# MCU.net
KiCad netlist of a schematic drawn in Altium Designer
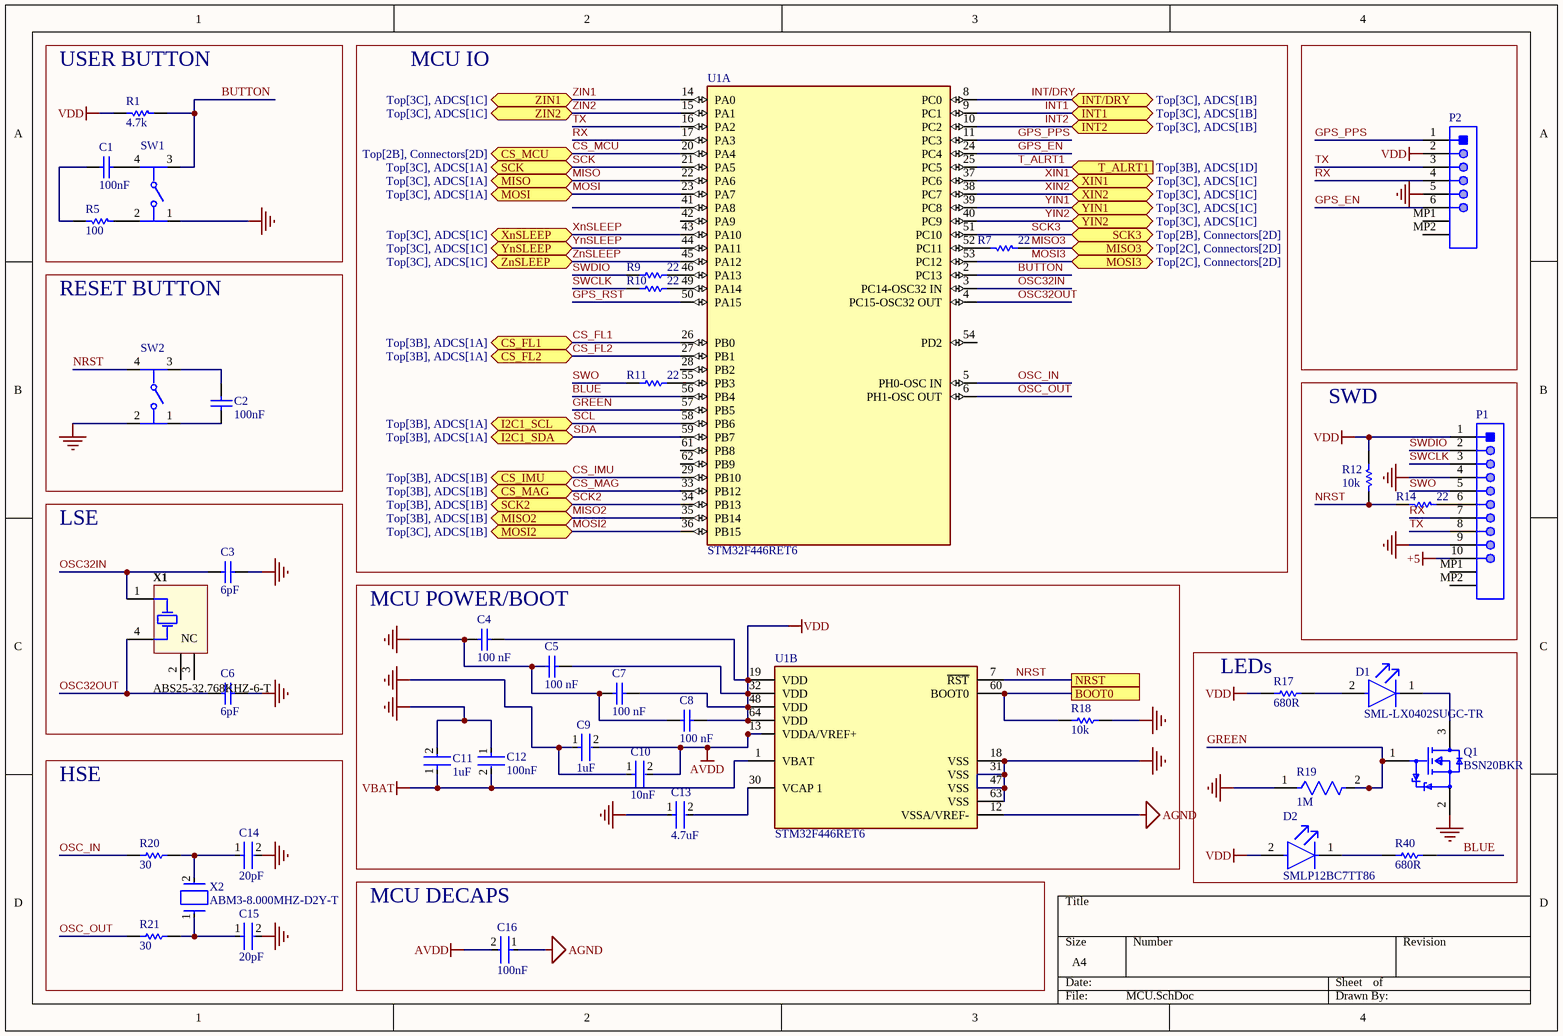
[diagram p0: MCU.SchDoc]

(export (version "E")
  (design (tool "Eeschema 10.0.6"))
  (components
    (comp (ref "C1")
      (value "100nF")
      (footprint "CAPC1050X55X23ML05T13")
      (description "Chip Capacitor, 100 nF, +/- 10%, 16 V, -55 to 125 degC, 0402 (1005 Metric), RoHS, Tape and Reel")
      (fields (field (name "MANUFACTURER") "Samsung Electro-Mechanics"))
      (libsource (lib "Altium Content Vault") (part "CAP-NP-2"))
    )
    (comp (ref "C2")
      (value "100nF")
      (footprint "CAPC1050X55X23ML05T13")
      (description "Chip Capacitor, 100 nF, +/- 10%, 16 V, -55 to 125 degC, 0402 (1005 Metric), RoHS, Tape and Reel")
      (fields (field (name "MANUFACTURER") "Samsung Electro-Mechanics"))
      (libsource (lib "Altium Content Vault") (part "CAP-NP-2"))
    )
    (comp (ref "C3")
      (value "6pF")
      (footprint "CAPC1005X55X25ML05T10")
      (fields (field (name "PART NUMBER") "GRM1555C1H6R0DA01D") (field (name "MANUFACTURER") "Murata"))
      (libsource (lib "Altium Content Vault") (part "CAP"))
    )
    (comp (ref "C4")
      (value "100 nF")
      (footprint "CAPC1050X55X23ML05T13")
      (description "Chip Capacitor, 100 nF, +/- 10%, 16 V, -55 to 125 degC, 0402 (1005 Metric), RoHS, Tape and Reel")
      (fields (field (name "MANUFACTURER") "Samsung Electro-Mechanics"))
      (libsource (lib "Altium Content Vault") (part "CAP-NP-2"))
    )
    (comp (ref "C5")
      (value "100 nF")
      (footprint "CAPC1050X55X23ML05T13")
      (description "Chip Capacitor, 100 nF, +/- 10%, 16 V, -55 to 125 degC, 0402 (1005 Metric), RoHS, Tape and Reel")
      (fields (field (name "MANUFACTURER") "Samsung Electro-Mechanics"))
      (libsource (lib "Altium Content Vault") (part "CAP-NP-2"))
    )
    (comp (ref "C6")
      (value "6pF")
      (footprint "CAPC1005X55X25ML05T10")
      (fields (field (name "PART NUMBER") "GRM1555C1H6R0DA01D") (field (name "MANUFACTURER") "Murata"))
      (libsource (lib "Altium Content Vault") (part "CAP"))
    )
    (comp (ref "C7")
      (value "100 nF")
      (footprint "CAPC1050X55X23ML05T13")
      (description "Chip Capacitor, 100 nF, +/- 10%, 16 V, -55 to 125 degC, 0402 (1005 Metric), RoHS, Tape and Reel")
      (fields (field (name "MANUFACTURER") "Samsung Electro-Mechanics"))
      (libsource (lib "Altium Content Vault") (part "CAP-NP-2"))
    )
    (comp (ref "C8")
      (value "100 nF")
      (footprint "CAPC1050X55X23ML05T13")
      (description "Chip Capacitor, 100 nF, +/- 10%, 16 V, -55 to 125 degC, 0402 (1005 Metric), RoHS, Tape and Reel")
      (fields (field (name "MANUFACTURER") "Samsung Electro-Mechanics"))
      (libsource (lib "Altium Content Vault") (part "CAP-NP-2"))
    )
    (comp (ref "C9")
      (value "1uF")
      (footprint "FP-CL10-IPC_A")
      (description "Cap Ceramic 1uF 16V X5R ±10% Pad SMD 0603 +85°C T/R")
      (fields (field (name "TOLERANCE") "10%") (field (name "VOLTAGE") "16V"))
      (libsource (lib "Altium Content Vault") (part "b4654b650e69147ec39a6b967a45e02"))
    )
    (comp (ref "C10")
      (value "10nF")
      (footprint "FP-CL165-IPC_C")
      (description "Cap Ceramic 10nF 50V X7R ±10% SMD 0402 +125°C Paper T/R")
      (fields (field (name "VOLTAGE") "50V") (field (name "TOLERANCE") "10%"))
      (libsource (lib "Altium Content Vault") (part "b4654b650e69147ec39a6b967a45e02"))
    )
    (comp (ref "C11")
      (value "1uF")
      (footprint "FP-CL10-IPC_C")
      (description "Cap Ceramic 1uF 25V X5R ±10% Pad SMD 0603 +85°C T/R")
      (fields (field (name "VOLTAGE") "25V") (field (name "TOLERANCE") "10%"))
      (libsource (lib "Altium Content Vault") (part "b4654b650e69147ec39a6b967a45e02"))
    )
    (comp (ref "C12")
      (value "100nF")
      (footprint "FP-CC0402-MFG")
      (description "CAP CER 0.1UF 16V X7R 0402")
      (fields (field (name "MANUFACTURER") "YAGEO") (field (name "TOLERANCE") "0.1"))
      (libsource (lib "Altium Content Vault") (part "11868f565c42a9108669ba33697ecf6"))
    )
    (comp (ref "C13")
      (value "4.7uF")
      (footprint "FP-CC0805-0_85-MFG")
      (description "CAP CER 4.7UF 16V X7R 0805")
      (fields
        (field (name "MANUFACTURER") "Yageo")
        (field (name "OCTOPART") "https://octopart.com/cc0805kkx7r7bb475-yageo-34429188")
      )
      (libsource (lib "Altium Content Vault") (part "11868f565c42a9108669ba33697ecf6"))
    )
    (comp (ref "C14")
      (value "20pF")
      (footprint "FP-CC0603-0_9-MFG")
      (description "CAP CER 20PF 50V C0G/NPO 0603")
      (fields (field (name "TOLERANCE") "5%"))
      (libsource (lib "Altium Content Vault") (part "b4654b650e69147ec39a6b967a45e02"))
    )
    (comp (ref "C15")
      (value "20pF")
      (footprint "FP-CC0603-0_9-MFG")
      (description "CAP CER 20PF 50V C0G/NPO 0603")
      (fields (field (name "TOLERANCE") "5%"))
      (libsource (lib "Altium Content Vault") (part "b4654b650e69147ec39a6b967a45e02"))
    )
    (comp (ref "C16")
      (value "100nF")
      (footprint "FP-CC0402-MFG")
      (description "CAP CER 0.1UF 16V X7R 0402")
      (fields (field (name "MANUFACTURER") "YAGEO") (field (name "TOLERANCE") "0.1"))
      (libsource (lib "Altium Content Vault") (part "11868f565c42a9108669ba33697ecf6"))
    )
    (comp (ref "D1")
      (value "SML-LX0402SUGC-TR")
      (footprint "FP-SML-LX0402SUGC-TR-MFG")
      (description "LED GREEN CLEAR SMD")
      (libsource (lib "Altium Content Vault") (part "8706943c75ba83719d021d2fdc84c58"))
    )
    (comp (ref "D2")
      (value "SMLP12BC7TT86")
      (footprint "FP-SML-P12-MFG")
      (description "LED BLUE CLEAR 1006 SMD")
      (fields
        (field (name "MANUFACTURER") "Rohm")
        (field (name "OCTOPART") "https://octopart.com/smlp12bc7tt86-rohm-9290887")
      )
      (libsource (lib "Altium Content Vault") (part "8706943c75ba83719d021d2fdc84c58"))
    )
    (comp (ref "P1")
      (value "SM10B-SHLS-TF(LF)(SN)")
      (footprint "JST-SM10B-SHLS-TF_V")
      (description "Male Header, Pitch 1 mm, 1 x 10 Position, Height 1.8 mm, -25 to 85 degC")
      (fields (field (name "MANUFACTURER") "JST"))
      (libsource (lib "Altium Content Vault") (part "CN-1P-2M-R10"))
    )
    (comp (ref "P2")
      (value "SM06B-SRSS-TB(LF)(SN)")
      (footprint "JST-SM06B-SRSS-TB_V")
      (description "Male Header, Pitch 1 mm, 1 x 6 Position, Height 2.95 mm, -25 to 85 degC, RoHS, Tape and Reel")
      (fields (field (name "MANUFACTURER") "JST"))
      (libsource (lib "Altium Content Vault") (part "CN-1P-2M-R6"))
    )
    (comp (ref "Q1")
      (value "BSN20BKR")
      (footprint "FP-SOT23-IPC_C")
      (description "MOSFET N-CH 60V 265MA TO236AB")
      (libsource (lib "Altium Content Vault") (part "9f09aa45b414195f9603f7520b00189"))
    )
    (comp (ref "R1")
      (value "4.7k")
      (footprint "RESC1005X40X25LL05T05")
      (description "Chip Resistor, 4.7 KOhm, +/- 1%, 0.1 W, -55 to 155 degC, 0402 (1005 Metric), RoHS, Tape and Reel")
      (fields (field (name "TOLERANCE") "1%") (field (name "PARTNUMBER") "ERJ-2RKF4701X"))
      (libsource (lib "Altium Content Vault") (part "RES-2"))
    )
    (comp (ref "R5")
      (value "100")
      (footprint "RESC1608X55X30LL15T15")
      (fields (field (name "MANUFACTURER") "Panasonic") (field (name "PART NUMBER") "ERJ-3EKF1000V"))
      (libsource (lib "Altium Content Vault") (part "RES"))
    )
    (comp (ref "R7")
      (value "22")
      (footprint "RESC1608X55X25NL10T15")
      (description "Chip Resistor, 22 Ohm, +/- 1%, 0.1 W, -55 to 155 degC, 0603 (1608 Metric), RoHS, Tape and Reel")
      (libsource (lib "Altium Content Vault") (part "RES-2"))
    )
    (comp (ref "R9")
      (value "22")
      (footprint "RESC1005X40X25ML05T05")
      (description "Chip Resistor, 22 Ohm, +/- 1%, 0.1 W, -55 to 155 degC, 0402 (1005 Metric), RoHS, Tape and Reel")
      (fields (field (name "PARTNUMBER") "ERJ-2RKF22R0X") (field (name "TOLERANCE") "1%"))
      (libsource (lib "Altium Content Vault") (part "RES-2"))
    )
    (comp (ref "R10")
      (value "22")
      (footprint "RESC1005X40X25ML05T05")
      (description "Chip Resistor, 22 Ohm, +/- 1%, 0.1 W, -55 to 155 degC, 0402 (1005 Metric), RoHS, Tape and Reel")
      (fields (field (name "PARTNUMBER") "ERJ-2RKF22R0X") (field (name "TOLERANCE") "1%"))
      (libsource (lib "Altium Content Vault") (part "RES-2"))
    )
    (comp (ref "R11")
      (value "22")
      (footprint "RESC1005X40X25ML05T05")
      (description "Chip Resistor, 22 Ohm, +/- 1%, 0.1 W, -55 to 155 degC, 0402 (1005 Metric), RoHS, Tape and Reel")
      (fields (field (name "PARTNUMBER") "ERJ-2RKF22R0X") (field (name "TOLERANCE") "1%"))
      (libsource (lib "Altium Content Vault") (part "RES-2"))
    )
    (comp (ref "R12")
      (value "10k")
      (footprint "RESC1005X40X25LL05T10")
      (fields (field (name "PART NUMBER") "RC0402FR-0710KL") (field (name "MANUFACTURER") "Yageo / Phycomp"))
      (libsource (lib "Altium Content Vault") (part "RES"))
    )
    (comp (ref "R14")
      (value "22")
      (footprint "RESC1608X55X25NL10T15")
      (description "Chip Resistor, 22 Ohm, +/- 1%, 0.1 W, -55 to 155 degC, 0603 (1608 Metric), RoHS, Tape and Reel")
      (libsource (lib "Altium Content Vault") (part "RES-2"))
    )
    (comp (ref "R17")
      (value "680R")
      (footprint "RESC1005X40X25ML05T05")
      (fields (field (name "MANUFACTURER") "Vishay Dale") (field (name "PART NUMBER") "CRCW0402680RFKED"))
      (libsource (lib "Altium Content Vault") (part "RES"))
    )
    (comp (ref "R18")
      (value "10k")
      (footprint "RESC1005X40X25LL05T05")
      (description "Chip Resistor, 10 KOhm, +/- 1%, 0.1 W, -55 to 155 degC, 0402 (1005 Metric), RoHS, Tape and Reel")
      (fields (field (name "TOLERANCE") "1%") (field (name "MANUFACTURER") "Panasonic"))
      (libsource (lib "Altium Content Vault") (part "RES-2"))
    )
    (comp (ref "R19")
      (value "1M")
      (footprint "FP-MCR01-IPC_B")
      (description "Thick Film Chip Resistor, 0402, 1MΩ, 1%, 100ppm/°C, 0.063W, 50V")
      (fields (field (name "TOLERANCE") "1%"))
      (libsource (lib "Altium Content Vault") (part "1029c3af85768c4190bb7ad29bc67b5"))
    )
    (comp (ref "R20")
      (value "30")
      (footprint "RESC1609X50X30NL10T20")
      (fields (field (name "PART NUMBER") "CRCW060330R0FKEA") (field (name "MANUFACTURER") "Vishay Dale"))
      (libsource (lib "Altium Content Vault") (part "RES"))
    )
    (comp (ref "R21")
      (value "30")
      (footprint "RESC1609X50X30NL10T20")
      (fields (field (name "PART NUMBER") "CRCW060330R0FKEA") (field (name "MANUFACTURER") "Vishay Dale"))
      (libsource (lib "Altium Content Vault") (part "RES"))
    )
    (comp (ref "R40")
      (value "680R")
      (footprint "RESC1005X40X25ML05T05")
      (fields (field (name "MANUFACTURER") "Vishay Dale") (field (name "PART NUMBER") "CRCW0402680RFKED"))
      (libsource (lib "Altium Content Vault") (part "RES"))
    )
    (comp (ref "SW1")
      (value "PTS810SJM250SMTRLFS")
      (footprint "FP-PTS810SJM250SMTRLFS-MFG")
      (description "SWITCH TACTILE SPST-NO 0.05A 16V")
      (libsource (lib "Altium Content Vault") (part "1adf0dd01260c80cf25a44bfd6b99ba"))
    )
    (comp (ref "SW2")
      (value "PTS810SJM250SMTRLFS")
      (footprint "FP-PTS810SJM250SMTRLFS-MFG")
      (description "SWITCH TACTILE SPST-NO 0.05A 16V")
      (libsource (lib "Altium Content Vault") (part "1adf0dd01260c80cf25a44bfd6b99ba"))
    )
    (comp (ref "U1")
      (value "STM32F446RET6")
      (footprint "FP-LQFP64-5W-MFG")
      (description "IC MCU 32BIT 512KB FLASH 64LQFP")
      (fields
        (field (name "OCTOPART") "https://octopart.com/stm32f446ret6-stmicroelectronics-52642920")
        (field (name "MANUFACTURER") "ST")
      )
      (libsource (lib "Altium Content Vault") (part "ee11adc32c0ab33b933cccf4348c338"))
    )
    (comp (ref "X1")
      (value "ABS25-32.768KHZ-6-T")
      (footprint "ABRA-ABS25-4_V")
      (fields (field (name "TOLERANCE") "20PPM") (field (name "MANUFACTURER") "Abracon"))
      (libsource (lib "Altium Content Vault") (part "ABRA-XTAL_1-4-4"))
    )
    (comp (ref "X2")
      (value "ABM3-8.000MHZ-D2Y-T")
      (footprint "FP-ABM3-MFG")
      (description "Crystal 8MHz ±20ppm 18pF SMD-2 5mm x 3.2mm")
      (fields (field (name "TOLERANCE") "20ppm"))
      (libsource (lib "Altium Content Vault") (part "c23a69dc6c9e2f18f2079038eb95dd1"))
    )
  )
  (nets
    (net (code "1") (name "+5") (class "Default")
      (node (ref "P1") (pin "10") (pinfunction "10_10") (pintype "passive"))
    )
    (net (code "2") (name "/BLUE") (class "Default")
      (node (ref "R40") (pin "2") (pinfunction "2_2") (pintype "passive"))
      (node (ref "U1") (pin "56") (pinfunction "PB4_56") (pintype "bidirectional"))
    )
    (net (code "3") (name "/BOOT0") (class "Default")
      (node (ref "R18") (pin "2") (pinfunction "2_2") (pintype "passive"))
      (node (ref "U1") (pin "60") (pinfunction "BOOT0_60") (pintype "input"))
    )
    (net (code "4") (name "/BUTTON") (class "Default")
      (node (ref "R1") (pin "1") (pinfunction "1_1") (pintype "passive"))
      (node (ref "SW1") (pin "3") (pinfunction "3_3") (pintype "passive"))
      (node (ref "U1") (pin "2") (pinfunction "PC13_2") (pintype "bidirectional"))
    )
    (net (code "5") (name "/CS_FL1") (class "Default")
      (node (ref "U1") (pin "26") (pinfunction "PB0_26") (pintype "bidirectional"))
    )
    (net (code "6") (name "/CS_FL2") (class "Default")
      (node (ref "U1") (pin "27") (pinfunction "PB1_27") (pintype "bidirectional"))
    )
    (net (code "7") (name "/CS_IMU") (class "Default")
      (node (ref "U1") (pin "29") (pinfunction "PB10_29") (pintype "bidirectional"))
    )
    (net (code "8") (name "/CS_MAG") (class "Default")
      (node (ref "U1") (pin "33") (pinfunction "PB12_33") (pintype "bidirectional"))
    )
    (net (code "9") (name "/CS_MCU") (class "Default")
      (node (ref "U1") (pin "20") (pinfunction "PA4_20") (pintype "bidirectional"))
    )
    (net (code "10") (name "/GPS_EN") (class "Default")
      (node (ref "P2") (pin "6") (pinfunction "6_6") (pintype "passive"))
      (node (ref "U1") (pin "24") (pinfunction "PC4_24") (pintype "bidirectional"))
    )
    (net (code "11") (name "/GPS_PPS") (class "Default")
      (node (ref "P2") (pin "1") (pinfunction "1_1") (pintype "passive"))
      (node (ref "U1") (pin "11") (pinfunction "PC3_11") (pintype "bidirectional"))
    )
    (net (code "12") (name "/GPS_RST") (class "Default")
      (node (ref "U1") (pin "50") (pinfunction "PA15_50") (pintype "bidirectional"))
    )
    (net (code "13") (name "/GREEN") (class "Default")
      (node (ref "Q1") (pin "1") (pinfunction "G_1") (pintype "passive"))
      (node (ref "R19") (pin "2") (pinfunction "2_2") (pintype "passive"))
      (node (ref "U1") (pin "57") (pinfunction "PB5_57") (pintype "bidirectional"))
    )
    (net (code "14") (name "/INT1") (class "Default")
      (node (ref "U1") (pin "9") (pinfunction "PC1_9") (pintype "bidirectional"))
    )
    (net (code "15") (name "/INT2") (class "Default")
      (node (ref "U1") (pin "10") (pinfunction "PC2_10") (pintype "bidirectional"))
    )
    (net (code "16") (name "/INT{slash}DRY") (class "Default")
      (node (ref "U1") (pin "8") (pinfunction "PC0_8") (pintype "bidirectional"))
    )
    (net (code "17") (name "/MISO") (class "Default")
      (node (ref "U1") (pin "22") (pinfunction "PA6_22") (pintype "bidirectional"))
    )
    (net (code "18") (name "/MISO2") (class "Default")
      (node (ref "U1") (pin "35") (pinfunction "PB14_35") (pintype "bidirectional"))
    )
    (net (code "19") (name "/MISO3") (class "Default")
      (node (ref "R7") (pin "1") (pinfunction "1_1") (pintype "passive"))
    )
    (net (code "20") (name "/MOSI") (class "Default")
      (node (ref "U1") (pin "23") (pinfunction "PA7_23") (pintype "bidirectional"))
    )
    (net (code "21") (name "/MOSI2") (class "Default")
      (node (ref "U1") (pin "36") (pinfunction "PB15_36") (pintype "bidirectional"))
    )
    (net (code "22") (name "/MOSI3") (class "Default")
      (node (ref "U1") (pin "53") (pinfunction "PC12_53") (pintype "bidirectional"))
    )
    (net (code "23") (name "/NRST") (class "Default")
      (node (ref "R12") (pin "2") (pinfunction "2_2") (pintype "passive"))
      (node (ref "R14") (pin "2") (pinfunction "2_2") (pintype "passive"))
      (node (ref "SW2") (pin "4") (pinfunction "4_4") (pintype "passive"))
      (node (ref "U1") (pin "7") (pinfunction "~{RST}_7") (pintype "input"))
    )
    (net (code "24") (name "/OSC32IN") (class "Default")
      (node (ref "C3") (pin "1") (pinfunction "1_1") (pintype "passive"))
      (node (ref "U1") (pin "3") (pinfunction "PC14-OSC32_IN_3") (pintype "bidirectional"))
      (node (ref "X1") (pin "1") (pinfunction "X1_1") (pintype "passive"))
    )
    (net (code "25") (name "/OSC32OUT") (class "Default")
      (node (ref "C6") (pin "1") (pinfunction "1_1") (pintype "passive"))
      (node (ref "U1") (pin "4") (pinfunction "PC15-OSC32_OUT_4") (pintype "bidirectional"))
      (node (ref "X1") (pin "4") (pinfunction "X2_4") (pintype "passive"))
    )
    (net (code "26") (name "/OSC_IN") (class "Default")
      (node (ref "R20") (pin "1") (pinfunction "1_1") (pintype "passive"))
      (node (ref "U1") (pin "5") (pinfunction "PH0-OSC_IN_5") (pintype "bidirectional"))
    )
    (net (code "27") (name "/OSC_OUT") (class "Default")
      (node (ref "R21") (pin "1") (pinfunction "1_1") (pintype "passive"))
      (node (ref "U1") (pin "6") (pinfunction "PH1-OSC_OUT_6") (pintype "bidirectional"))
    )
    (net (code "28") (name "/RX") (class "Default")
      (node (ref "P1") (pin "7") (pinfunction "7_7") (pintype "passive"))
      (node (ref "P2") (pin "4") (pinfunction "4_4") (pintype "passive"))
      (node (ref "U1") (pin "17") (pinfunction "PA3_17") (pintype "bidirectional"))
    )
    (net (code "29") (name "/SCK") (class "Default")
      (node (ref "U1") (pin "21") (pinfunction "PA5_21") (pintype "bidirectional"))
    )
    (net (code "30") (name "/SCK2") (class "Default")
      (node (ref "U1") (pin "34") (pinfunction "PB13_34") (pintype "bidirectional"))
    )
    (net (code "31") (name "/SCK3") (class "Default")
      (node (ref "U1") (pin "51") (pinfunction "PC10_51") (pintype "bidirectional"))
    )
    (net (code "32") (name "/SCL") (class "Default")
      (node (ref "U1") (pin "58") (pinfunction "PB6_58") (pintype "bidirectional"))
    )
    (net (code "33") (name "/SDA") (class "Default")
      (node (ref "U1") (pin "59") (pinfunction "PB7_59") (pintype "bidirectional"))
    )
    (net (code "34") (name "/SWCLK") (class "Default")
      (node (ref "P1") (pin "3") (pinfunction "3_3") (pintype "passive"))
      (node (ref "R10") (pin "1") (pinfunction "1_1") (pintype "passive"))
    )
    (net (code "35") (name "/SWDIO") (class "Default")
      (node (ref "P1") (pin "2") (pinfunction "2_2") (pintype "passive"))
      (node (ref "R9") (pin "1") (pinfunction "1_1") (pintype "passive"))
    )
    (net (code "36") (name "/SWO") (class "Default")
      (node (ref "P1") (pin "5") (pinfunction "5_5") (pintype "passive"))
      (node (ref "R11") (pin "1") (pinfunction "1_1") (pintype "passive"))
    )
    (net (code "37") (name "/TX") (class "Default")
      (node (ref "P1") (pin "8") (pinfunction "8_8") (pintype "passive"))
      (node (ref "P2") (pin "3") (pinfunction "3_3") (pintype "passive"))
      (node (ref "U1") (pin "16") (pinfunction "PA2_16") (pintype "bidirectional"))
    )
    (net (code "38") (name "/T_ALRT1") (class "Default")
      (node (ref "U1") (pin "25") (pinfunction "PC5_25") (pintype "bidirectional"))
    )
    (net (code "39") (name "/XIN1") (class "Default")
      (node (ref "U1") (pin "37") (pinfunction "PC6_37") (pintype "bidirectional"))
    )
    (net (code "40") (name "/XIN2") (class "Default")
      (node (ref "U1") (pin "38") (pinfunction "PC7_38") (pintype "bidirectional"))
    )
    (net (code "41") (name "/XnSLEEP") (class "Default")
      (node (ref "U1") (pin "43") (pinfunction "PA10_43") (pintype "bidirectional"))
    )
    (net (code "42") (name "/YIN1") (class "Default")
      (node (ref "U1") (pin "39") (pinfunction "PC8_39") (pintype "bidirectional"))
    )
    (net (code "43") (name "/YIN2") (class "Default")
      (node (ref "U1") (pin "40") (pinfunction "PC9_40") (pintype "bidirectional"))
    )
    (net (code "44") (name "/YnSLEEP") (class "Default")
      (node (ref "U1") (pin "44") (pinfunction "PA11_44") (pintype "bidirectional"))
    )
    (net (code "45") (name "/ZIN1") (class "Default")
      (node (ref "U1") (pin "14") (pinfunction "PA0_14") (pintype "bidirectional"))
    )
    (net (code "46") (name "/ZIN2") (class "Default")
      (node (ref "U1") (pin "15") (pinfunction "PA1_15") (pintype "bidirectional"))
    )
    (net (code "47") (name "/ZnSLEEP") (class "Default")
      (node (ref "U1") (pin "45") (pinfunction "PA12_45") (pintype "bidirectional"))
    )
    (net (code "48") (name "AGND") (class "Default")
      (node (ref "C16") (pin "1") (pinfunction "1_1") (pintype "passive"))
      (node (ref "U1") (pin "12") (pinfunction "VSSA/VREF-_12") (pintype "power_in"))
    )
    (net (code "49") (name "AVDD") (class "Default")
      (node (ref "C10") (pin "2") (pinfunction "2_2") (pintype "passive"))
      (node (ref "C16") (pin "2") (pinfunction "2_2") (pintype "passive"))
      (node (ref "C9") (pin "2") (pinfunction "2_2") (pintype "passive"))
      (node (ref "U1") (pin "13") (pinfunction "VDDA/VREF+_13") (pintype "power_in"))
    )
    (net (code "50") (name "GND") (class "Default")
      (node (ref "C10") (pin "1") (pinfunction "1_1") (pintype "passive"))
      (node (ref "C11") (pin "2") (pinfunction "2_2") (pintype "passive"))
      (node (ref "C12") (pin "1") (pinfunction "1_1") (pintype "passive"))
      (node (ref "C13") (pin "1") (pinfunction "1_1") (pintype "passive"))
      (node (ref "C14") (pin "2") (pinfunction "2_2") (pintype "passive"))
      (node (ref "C15") (pin "2") (pinfunction "2_2") (pintype "passive"))
      (node (ref "C3") (pin "2") (pinfunction "2_2") (pintype "passive"))
      (node (ref "C4") (pin "1") (pinfunction "1_1") (pintype "passive"))
      (node (ref "C5") (pin "1") (pinfunction "1_1") (pintype "passive"))
      (node (ref "C6") (pin "2") (pinfunction "2_2") (pintype "passive"))
      (node (ref "C7") (pin "1") (pinfunction "1_1") (pintype "passive"))
      (node (ref "C8") (pin "1") (pinfunction "1_1") (pintype "passive"))
      (node (ref "C9") (pin "1") (pinfunction "1_1") (pintype "passive"))
      (node (ref "P1") (pin "4") (pinfunction "4_4") (pintype "passive"))
      (node (ref "P1") (pin "9") (pinfunction "9_9") (pintype "passive"))
      (node (ref "P2") (pin "5") (pinfunction "5_5") (pintype "passive"))
      (node (ref "Q1") (pin "2") (pinfunction "S_2") (pintype "passive"))
      (node (ref "R18") (pin "1") (pinfunction "1_1") (pintype "passive"))
      (node (ref "R19") (pin "1") (pinfunction "1_1") (pintype "passive"))
      (node (ref "SW1") (pin "1") (pinfunction "1_1") (pintype "passive"))
      (node (ref "SW2") (pin "2") (pinfunction "2_2") (pintype "passive"))
      (node (ref "U1") (pin "18") (pinfunction "VSS_18") (pintype "power_in"))
      (node (ref "U1") (pin "31") (pinfunction "VSS_31") (pintype "power_in"))
      (node (ref "U1") (pin "47") (pinfunction "VSS_47") (pintype "power_in"))
      (node (ref "U1") (pin "63") (pinfunction "VSS_63") (pintype "power_in"))
    )
    (net (code "51") (name "Net-(C1-Pad1)") (class "Default")
      (node (ref "C1") (pin "1") (pinfunction "1_1") (pintype "passive"))
      (node (ref "SW1") (pin "4") (pinfunction "4_4") (pintype "passive"))
    )
    (net (code "52") (name "Net-(C1-Pad2)") (class "Default")
      (node (ref "C1") (pin "2") (pinfunction "2_2") (pintype "passive"))
      (node (ref "R5") (pin "2") (pinfunction "2_2") (pintype "passive"))
    )
    (net (code "53") (name "Net-(C2-Pad1)") (class "Default")
      (node (ref "C2") (pin "1") (pinfunction "1_1") (pintype "passive"))
      (node (ref "SW2") (pin "1") (pinfunction "1_1") (pintype "passive"))
    )
    (net (code "54") (name "Net-(C2-Pad2)") (class "Default")
      (node (ref "C2") (pin "2") (pinfunction "2_2") (pintype "passive"))
      (node (ref "SW2") (pin "3") (pinfunction "3_3") (pintype "passive"))
    )
    (net (code "55") (name "Net-(C14-Pad1)") (class "Default")
      (node (ref "C14") (pin "1") (pinfunction "1_1") (pintype "passive"))
      (node (ref "R20") (pin "2") (pinfunction "2_2") (pintype "passive"))
      (node (ref "X2") (pin "2") (pinfunction "2_2") (pintype "passive"))
    )
    (net (code "56") (name "Net-(C15-Pad1)") (class "Default")
      (node (ref "C15") (pin "1") (pinfunction "1_1") (pintype "passive"))
      (node (ref "R21") (pin "2") (pinfunction "2_2") (pintype "passive"))
      (node (ref "X2") (pin "1") (pinfunction "1_1") (pintype "passive"))
    )
    (net (code "57") (name "Net-(D1-A)") (class "Default")
      (node (ref "D1") (pin "2") (pinfunction "A_2") (pintype "passive"))
      (node (ref "R17") (pin "2") (pinfunction "2_2") (pintype "passive"))
    )
    (net (code "58") (name "Net-(D1-C)") (class "Default")
      (node (ref "D1") (pin "1") (pinfunction "C_1") (pintype "passive"))
      (node (ref "Q1") (pin "3") (pinfunction "D_3") (pintype "passive"))
    )
    (net (code "59") (name "Net-(D2-C)") (class "Default")
      (node (ref "D2") (pin "1") (pinfunction "C_1") (pintype "passive"))
      (node (ref "R40") (pin "1") (pinfunction "1_1") (pintype "passive"))
    )
    (net (code "60") (name "Net-(P1-Pad6)") (class "Default")
      (node (ref "P1") (pin "6") (pinfunction "6_6") (pintype "passive"))
      (node (ref "R14") (pin "1") (pinfunction "1_1") (pintype "passive"))
    )
    (net (code "61") (name "Net-(R5-Pad1)") (class "Default")
      (node (ref "R5") (pin "1") (pinfunction "1_1") (pintype "passive"))
      (node (ref "SW1") (pin "2") (pinfunction "2_2") (pintype "passive"))
    )
    (net (code "62") (name "Net-(U1A-PA13)") (class "Default")
      (node (ref "R9") (pin "2") (pinfunction "2_2") (pintype "passive"))
      (node (ref "U1") (pin "46") (pinfunction "PA13_46") (pintype "bidirectional"))
    )
    (net (code "63") (name "Net-(U1A-PA14)") (class "Default")
      (node (ref "R10") (pin "2") (pinfunction "2_2") (pintype "passive"))
      (node (ref "U1") (pin "49") (pinfunction "PA14_49") (pintype "bidirectional"))
    )
    (net (code "64") (name "Net-(U1A-PB3)") (class "Default")
      (node (ref "R11") (pin "2") (pinfunction "2_2") (pintype "passive"))
      (node (ref "U1") (pin "55") (pinfunction "PB3_55") (pintype "bidirectional"))
    )
    (net (code "65") (name "Net-(U1A-PC11)") (class "Default")
      (node (ref "R7") (pin "2") (pinfunction "2_2") (pintype "passive"))
      (node (ref "U1") (pin "52") (pinfunction "PC11_52") (pintype "bidirectional"))
    )
    (net (code "66") (name "Net-(U1B-VCAP_1)") (class "Default")
      (node (ref "C13") (pin "2") (pinfunction "2_2") (pintype "passive"))
      (node (ref "U1") (pin "30") (pinfunction "VCAP_1_30") (pintype "power_in"))
    )
    (net (code "67") (name "VBAT") (class "Default")
      (node (ref "C11") (pin "1") (pinfunction "1_1") (pintype "passive"))
      (node (ref "C12") (pin "2") (pinfunction "2_2") (pintype "passive"))
      (node (ref "U1") (pin "1") (pinfunction "VBAT_1") (pintype "power_in"))
    )
    (net (code "68") (name "VDD") (class "Default")
      (node (ref "C4") (pin "2") (pinfunction "2_2") (pintype "passive"))
      (node (ref "C5") (pin "2") (pinfunction "2_2") (pintype "passive"))
      (node (ref "C7") (pin "2") (pinfunction "2_2") (pintype "passive"))
      (node (ref "C8") (pin "2") (pinfunction "2_2") (pintype "passive"))
      (node (ref "D2") (pin "2") (pinfunction "A_2") (pintype "passive"))
      (node (ref "P1") (pin "1") (pinfunction "1_1") (pintype "passive"))
      (node (ref "P2") (pin "2") (pinfunction "2_2") (pintype "passive"))
      (node (ref "R1") (pin "2") (pinfunction "2_2") (pintype "passive"))
      (node (ref "R12") (pin "1") (pinfunction "1_1") (pintype "passive"))
      (node (ref "R17") (pin "1") (pinfunction "1_1") (pintype "passive"))
      (node (ref "U1") (pin "19") (pinfunction "VDD_19") (pintype "power_in"))
      (node (ref "U1") (pin "32") (pinfunction "VDD_32") (pintype "power_in"))
      (node (ref "U1") (pin "48") (pinfunction "VDD_48") (pintype "power_in"))
      (node (ref "U1") (pin "64") (pinfunction "VDD_64") (pintype "power_in"))
    )
    (net (code "69") (name "unconnected-(P1-PadMP1)") (class "Default")
      (node (ref "P1") (pin "MP1") (pinfunction "MP1_MP1") (pintype "passive"))
    )
    (net (code "70") (name "unconnected-(P1-PadMP2)") (class "Default")
      (node (ref "P1") (pin "MP2") (pinfunction "MP2_MP2") (pintype "passive"))
    )
    (net (code "71") (name "unconnected-(P2-PadMP1)") (class "Default")
      (node (ref "P2") (pin "MP1") (pinfunction "MP1_MP1") (pintype "passive"))
    )
    (net (code "72") (name "unconnected-(P2-PadMP2)") (class "Default")
      (node (ref "P2") (pin "MP2") (pinfunction "MP2_MP2") (pintype "passive"))
    )
    (net (code "73") (name "unconnected-(U1A-PA8-Pad41)") (class "Default")
      (node (ref "U1") (pin "41") (pinfunction "PA8_41") (pintype "bidirectional"))
    )
    (net (code "74") (name "unconnected-(U1A-PA9-Pad42)") (class "Default")
      (node (ref "U1") (pin "42") (pinfunction "PA9_42") (pintype "bidirectional"))
    )
    (net (code "75") (name "unconnected-(U1A-PB2-Pad28)") (class "Default")
      (node (ref "U1") (pin "28") (pinfunction "PB2_28") (pintype "bidirectional"))
    )
    (net (code "76") (name "unconnected-(U1A-PB8-Pad61)") (class "Default")
      (node (ref "U1") (pin "61") (pinfunction "PB8_61") (pintype "bidirectional"))
    )
    (net (code "77") (name "unconnected-(U1A-PB9-Pad62)") (class "Default")
      (node (ref "U1") (pin "62") (pinfunction "PB9_62") (pintype "bidirectional"))
    )
    (net (code "78") (name "unconnected-(U1A-PD2-Pad54)") (class "Default")
      (node (ref "U1") (pin "54") (pinfunction "PD2_54") (pintype "bidirectional"))
    )
    (net (code "79") (name "unconnected-(X1-NC-Pad2)") (class "Default")
      (node (ref "X1") (pin "2") (pinfunction "NC_2") (pintype "passive"))
    )
    (net (code "80") (name "unconnected-(X1-NC-Pad3)") (class "Default")
      (node (ref "X1") (pin "3") (pinfunction "NC_3") (pintype "passive"))
    )
  )
)
